# LPDDR4_SDRAM_-_2.net
KiCad netlist of a schematic drawn in Altium Designer
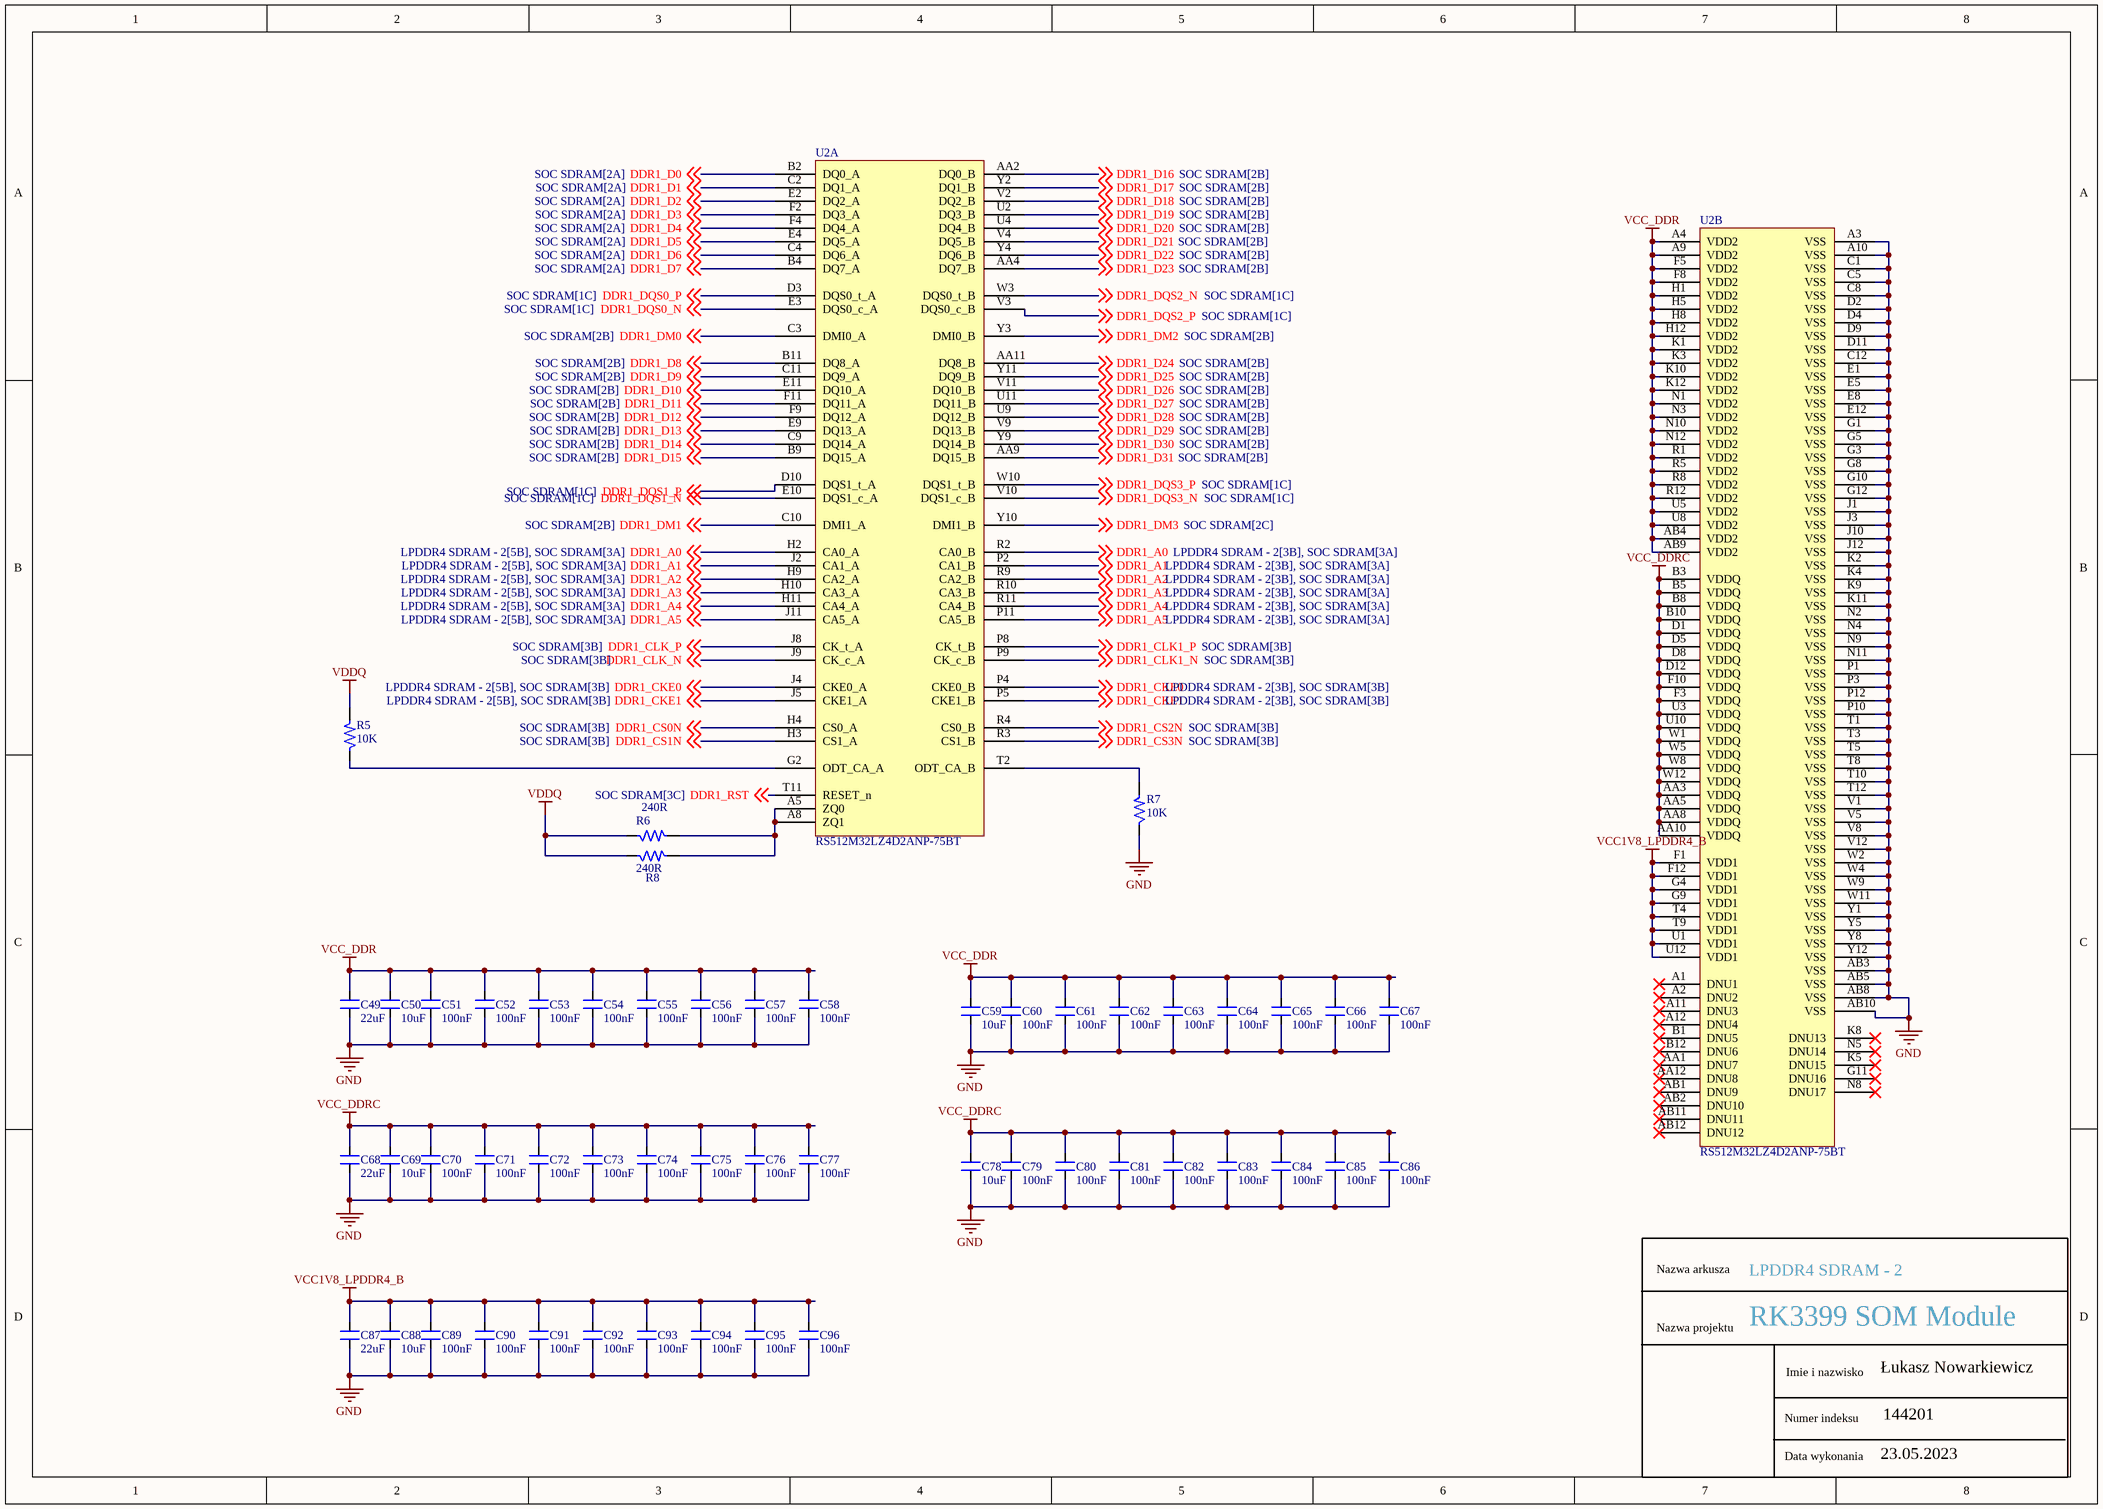
[diagram p0: LPDDR4 SDRAM - 2.SchDoc]

(export (version "E")
  (design (tool "Eeschema 10.0.6"))
  (components
    (comp (ref "C49")
      (value "22uF")
      (footprint "CAP_0603")
      (description "22µF ±20% 10V Ceramic Capacitor X5R 0603 (1608 Metric)")
      (fields
        (field (name "MANUFACTURER") "Murata Electronics")
        (field (name "MANUFACTURER PART NUMBER") "GRM188R61A226ME15D")
      )
      (libsource (lib "EsteemPCB_SOM_Course_intlib") (part "CAP_22uF-10V-20%-0603"))
    )
    (comp (ref "C50")
      (value "10uF")
      (footprint "CAP_0603")
      (description "10µF ±10% 10V Ceramic Capacitor X5R 0603 (1608 Metric)")
      (fields
        (field (name "MANUFACTURER PART NUMBER") "GRM188R61A106KE69J")
        (field (name "MANUFACTURER") "Murata Electronics")
      )
      (libsource (lib "EsteemPCB_SOM_Course_intlib") (part "CAP_10uF-10V-10%-0603"))
    )
    (comp (ref "C51")
      (value "100nF")
      (footprint "CAP_0402")
      (description "0.1µF ±10% 10V Ceramic Capacitor X7R 0402 (1005 Metric)")
      (fields
        (field (name "MANUFACTURER") "Yageo")
        (field (name "MANUFACTURER PART NUMBER") "CC0402KRX7R6BB104")
      )
      (libsource (lib "EsteemPCB_SOM_Course_intlib") (part "CAP_100nF-10V-10%-0402"))
    )
    (comp (ref "C52")
      (value "100nF")
      (footprint "CAP_0402")
      (description "0.1µF ±10% 10V Ceramic Capacitor X7R 0402 (1005 Metric)")
      (fields
        (field (name "MANUFACTURER") "Yageo")
        (field (name "MANUFACTURER PART NUMBER") "CC0402KRX7R6BB104")
      )
      (libsource (lib "EsteemPCB_SOM_Course_intlib") (part "CAP_100nF-10V-10%-0402"))
    )
    (comp (ref "C53")
      (value "100nF")
      (footprint "CAP_0402")
      (description "0.1µF ±10% 10V Ceramic Capacitor X7R 0402 (1005 Metric)")
      (fields
        (field (name "MANUFACTURER") "Yageo")
        (field (name "MANUFACTURER PART NUMBER") "CC0402KRX7R6BB104")
      )
      (libsource (lib "EsteemPCB_SOM_Course_intlib") (part "CAP_100nF-10V-10%-0402"))
    )
    (comp (ref "C54")
      (value "100nF")
      (footprint "CAP_0402")
      (description "0.1µF ±10% 10V Ceramic Capacitor X7R 0402 (1005 Metric)")
      (fields
        (field (name "MANUFACTURER") "Yageo")
        (field (name "MANUFACTURER PART NUMBER") "CC0402KRX7R6BB104")
      )
      (libsource (lib "EsteemPCB_SOM_Course_intlib") (part "CAP_100nF-10V-10%-0402"))
    )
    (comp (ref "C55")
      (value "100nF")
      (footprint "CAP_0402")
      (description "0.1µF ±10% 10V Ceramic Capacitor X7R 0402 (1005 Metric)")
      (fields
        (field (name "MANUFACTURER") "Yageo")
        (field (name "MANUFACTURER PART NUMBER") "CC0402KRX7R6BB104")
      )
      (libsource (lib "EsteemPCB_SOM_Course_intlib") (part "CAP_100nF-10V-10%-0402"))
    )
    (comp (ref "C56")
      (value "100nF")
      (footprint "CAP_0402")
      (description "0.1µF ±10% 10V Ceramic Capacitor X7R 0402 (1005 Metric)")
      (fields
        (field (name "MANUFACTURER") "Yageo")
        (field (name "MANUFACTURER PART NUMBER") "CC0402KRX7R6BB104")
      )
      (libsource (lib "EsteemPCB_SOM_Course_intlib") (part "CAP_100nF-10V-10%-0402"))
    )
    (comp (ref "C57")
      (value "100nF")
      (footprint "CAP_0402")
      (description "0.1µF ±10% 10V Ceramic Capacitor X7R 0402 (1005 Metric)")
      (fields
        (field (name "MANUFACTURER") "Yageo")
        (field (name "MANUFACTURER PART NUMBER") "CC0402KRX7R6BB104")
      )
      (libsource (lib "EsteemPCB_SOM_Course_intlib") (part "CAP_100nF-10V-10%-0402"))
    )
    (comp (ref "C58")
      (value "100nF")
      (footprint "CAP_0402")
      (description "0.1µF ±10% 10V Ceramic Capacitor X7R 0402 (1005 Metric)")
      (fields
        (field (name "MANUFACTURER") "Yageo")
        (field (name "MANUFACTURER PART NUMBER") "CC0402KRX7R6BB104")
      )
      (libsource (lib "EsteemPCB_SOM_Course_intlib") (part "CAP_100nF-10V-10%-0402"))
    )
    (comp (ref "C59")
      (value "10uF")
      (footprint "CAP_0603")
      (description "10µF ±10% 10V Ceramic Capacitor X5R 0603 (1608 Metric)")
      (fields
        (field (name "MANUFACTURER PART NUMBER") "GRM188R61A106KE69J")
        (field (name "MANUFACTURER") "Murata Electronics")
      )
      (libsource (lib "EsteemPCB_SOM_Course_intlib") (part "CAP_10uF-10V-10%-0603"))
    )
    (comp (ref "C60")
      (value "100nF")
      (footprint "CAP_0402")
      (description "0.1µF ±10% 10V Ceramic Capacitor X7R 0402 (1005 Metric)")
      (fields
        (field (name "MANUFACTURER") "Yageo")
        (field (name "MANUFACTURER PART NUMBER") "CC0402KRX7R6BB104")
      )
      (libsource (lib "EsteemPCB_SOM_Course_intlib") (part "CAP_100nF-10V-10%-0402"))
    )
    (comp (ref "C61")
      (value "100nF")
      (footprint "CAP_0402")
      (description "0.1µF ±10% 10V Ceramic Capacitor X7R 0402 (1005 Metric)")
      (fields
        (field (name "MANUFACTURER") "Yageo")
        (field (name "MANUFACTURER PART NUMBER") "CC0402KRX7R6BB104")
      )
      (libsource (lib "EsteemPCB_SOM_Course_intlib") (part "CAP_100nF-10V-10%-0402"))
    )
    (comp (ref "C62")
      (value "100nF")
      (footprint "CAP_0402")
      (description "0.1µF ±10% 10V Ceramic Capacitor X7R 0402 (1005 Metric)")
      (fields
        (field (name "MANUFACTURER") "Yageo")
        (field (name "MANUFACTURER PART NUMBER") "CC0402KRX7R6BB104")
      )
      (libsource (lib "EsteemPCB_SOM_Course_intlib") (part "CAP_100nF-10V-10%-0402"))
    )
    (comp (ref "C63")
      (value "100nF")
      (footprint "CAP_0402")
      (description "0.1µF ±10% 10V Ceramic Capacitor X7R 0402 (1005 Metric)")
      (fields
        (field (name "MANUFACTURER") "Yageo")
        (field (name "MANUFACTURER PART NUMBER") "CC0402KRX7R6BB104")
      )
      (libsource (lib "EsteemPCB_SOM_Course_intlib") (part "CAP_100nF-10V-10%-0402"))
    )
    (comp (ref "C64")
      (value "100nF")
      (footprint "CAP_0402")
      (description "0.1µF ±10% 10V Ceramic Capacitor X7R 0402 (1005 Metric)")
      (fields
        (field (name "MANUFACTURER") "Yageo")
        (field (name "MANUFACTURER PART NUMBER") "CC0402KRX7R6BB104")
      )
      (libsource (lib "EsteemPCB_SOM_Course_intlib") (part "CAP_100nF-10V-10%-0402"))
    )
    (comp (ref "C65")
      (value "100nF")
      (footprint "CAP_0402")
      (description "0.1µF ±10% 10V Ceramic Capacitor X7R 0402 (1005 Metric)")
      (fields
        (field (name "MANUFACTURER") "Yageo")
        (field (name "MANUFACTURER PART NUMBER") "CC0402KRX7R6BB104")
      )
      (libsource (lib "EsteemPCB_SOM_Course_intlib") (part "CAP_100nF-10V-10%-0402"))
    )
    (comp (ref "C66")
      (value "100nF")
      (footprint "CAP_0402")
      (description "0.1µF ±10% 10V Ceramic Capacitor X7R 0402 (1005 Metric)")
      (fields
        (field (name "MANUFACTURER") "Yageo")
        (field (name "MANUFACTURER PART NUMBER") "CC0402KRX7R6BB104")
      )
      (libsource (lib "EsteemPCB_SOM_Course_intlib") (part "CAP_100nF-10V-10%-0402"))
    )
    (comp (ref "C67")
      (value "100nF")
      (footprint "CAP_0402")
      (description "0.1µF ±10% 10V Ceramic Capacitor X7R 0402 (1005 Metric)")
      (fields
        (field (name "MANUFACTURER") "Yageo")
        (field (name "MANUFACTURER PART NUMBER") "CC0402KRX7R6BB104")
      )
      (libsource (lib "EsteemPCB_SOM_Course_intlib") (part "CAP_100nF-10V-10%-0402"))
    )
    (comp (ref "C68")
      (value "22uF")
      (footprint "CAP_0603")
      (description "22µF ±20% 10V Ceramic Capacitor X5R 0603 (1608 Metric)")
      (fields
        (field (name "MANUFACTURER") "Murata Electronics")
        (field (name "MANUFACTURER PART NUMBER") "GRM188R61A226ME15D")
      )
      (libsource (lib "EsteemPCB_SOM_Course_intlib") (part "CAP_22uF-10V-20%-0603"))
    )
    (comp (ref "C69")
      (value "10uF")
      (footprint "CAP_0603")
      (description "10µF ±10% 10V Ceramic Capacitor X5R 0603 (1608 Metric)")
      (fields
        (field (name "MANUFACTURER PART NUMBER") "GRM188R61A106KE69J")
        (field (name "MANUFACTURER") "Murata Electronics")
      )
      (libsource (lib "EsteemPCB_SOM_Course_intlib") (part "CAP_10uF-10V-10%-0603"))
    )
    (comp (ref "C70")
      (value "100nF")
      (footprint "CAP_0402")
      (description "0.1µF ±10% 10V Ceramic Capacitor X7R 0402 (1005 Metric)")
      (fields
        (field (name "MANUFACTURER") "Yageo")
        (field (name "MANUFACTURER PART NUMBER") "CC0402KRX7R6BB104")
      )
      (libsource (lib "EsteemPCB_SOM_Course_intlib") (part "CAP_100nF-10V-10%-0402"))
    )
    (comp (ref "C71")
      (value "100nF")
      (footprint "CAP_0402")
      (description "0.1µF ±10% 10V Ceramic Capacitor X7R 0402 (1005 Metric)")
      (fields
        (field (name "MANUFACTURER") "Yageo")
        (field (name "MANUFACTURER PART NUMBER") "CC0402KRX7R6BB104")
      )
      (libsource (lib "EsteemPCB_SOM_Course_intlib") (part "CAP_100nF-10V-10%-0402"))
    )
    (comp (ref "C72")
      (value "100nF")
      (footprint "CAP_0402")
      (description "0.1µF ±10% 10V Ceramic Capacitor X7R 0402 (1005 Metric)")
      (fields
        (field (name "MANUFACTURER") "Yageo")
        (field (name "MANUFACTURER PART NUMBER") "CC0402KRX7R6BB104")
      )
      (libsource (lib "EsteemPCB_SOM_Course_intlib") (part "CAP_100nF-10V-10%-0402"))
    )
    (comp (ref "C73")
      (value "100nF")
      (footprint "CAP_0402")
      (description "0.1µF ±10% 10V Ceramic Capacitor X7R 0402 (1005 Metric)")
      (fields
        (field (name "MANUFACTURER") "Yageo")
        (field (name "MANUFACTURER PART NUMBER") "CC0402KRX7R6BB104")
      )
      (libsource (lib "EsteemPCB_SOM_Course_intlib") (part "CAP_100nF-10V-10%-0402"))
    )
    (comp (ref "C74")
      (value "100nF")
      (footprint "CAP_0402")
      (description "0.1µF ±10% 10V Ceramic Capacitor X7R 0402 (1005 Metric)")
      (fields
        (field (name "MANUFACTURER") "Yageo")
        (field (name "MANUFACTURER PART NUMBER") "CC0402KRX7R6BB104")
      )
      (libsource (lib "EsteemPCB_SOM_Course_intlib") (part "CAP_100nF-10V-10%-0402"))
    )
    (comp (ref "C75")
      (value "100nF")
      (footprint "CAP_0402")
      (description "0.1µF ±10% 10V Ceramic Capacitor X7R 0402 (1005 Metric)")
      (fields
        (field (name "MANUFACTURER") "Yageo")
        (field (name "MANUFACTURER PART NUMBER") "CC0402KRX7R6BB104")
      )
      (libsource (lib "EsteemPCB_SOM_Course_intlib") (part "CAP_100nF-10V-10%-0402"))
    )
    (comp (ref "C76")
      (value "100nF")
      (footprint "CAP_0402")
      (description "0.1µF ±10% 10V Ceramic Capacitor X7R 0402 (1005 Metric)")
      (fields
        (field (name "MANUFACTURER") "Yageo")
        (field (name "MANUFACTURER PART NUMBER") "CC0402KRX7R6BB104")
      )
      (libsource (lib "EsteemPCB_SOM_Course_intlib") (part "CAP_100nF-10V-10%-0402"))
    )
    (comp (ref "C77")
      (value "100nF")
      (footprint "CAP_0402")
      (description "0.1µF ±10% 10V Ceramic Capacitor X7R 0402 (1005 Metric)")
      (fields
        (field (name "MANUFACTURER") "Yageo")
        (field (name "MANUFACTURER PART NUMBER") "CC0402KRX7R6BB104")
      )
      (libsource (lib "EsteemPCB_SOM_Course_intlib") (part "CAP_100nF-10V-10%-0402"))
    )
    (comp (ref "C78")
      (value "10uF")
      (footprint "CAP_0603")
      (description "10µF ±10% 10V Ceramic Capacitor X5R 0603 (1608 Metric)")
      (fields
        (field (name "MANUFACTURER PART NUMBER") "GRM188R61A106KE69J")
        (field (name "MANUFACTURER") "Murata Electronics")
      )
      (libsource (lib "EsteemPCB_SOM_Course_intlib") (part "CAP_10uF-10V-10%-0603"))
    )
    (comp (ref "C79")
      (value "100nF")
      (footprint "CAP_0402")
      (description "0.1µF ±10% 10V Ceramic Capacitor X7R 0402 (1005 Metric)")
      (fields
        (field (name "MANUFACTURER") "Yageo")
        (field (name "MANUFACTURER PART NUMBER") "CC0402KRX7R6BB104")
      )
      (libsource (lib "EsteemPCB_SOM_Course_intlib") (part "CAP_100nF-10V-10%-0402"))
    )
    (comp (ref "C80")
      (value "100nF")
      (footprint "CAP_0402")
      (description "0.1µF ±10% 10V Ceramic Capacitor X7R 0402 (1005 Metric)")
      (fields
        (field (name "MANUFACTURER") "Yageo")
        (field (name "MANUFACTURER PART NUMBER") "CC0402KRX7R6BB104")
      )
      (libsource (lib "EsteemPCB_SOM_Course_intlib") (part "CAP_100nF-10V-10%-0402"))
    )
    (comp (ref "C81")
      (value "100nF")
      (footprint "CAP_0402")
      (description "0.1µF ±10% 10V Ceramic Capacitor X7R 0402 (1005 Metric)")
      (fields
        (field (name "MANUFACTURER") "Yageo")
        (field (name "MANUFACTURER PART NUMBER") "CC0402KRX7R6BB104")
      )
      (libsource (lib "EsteemPCB_SOM_Course_intlib") (part "CAP_100nF-10V-10%-0402"))
    )
    (comp (ref "C82")
      (value "100nF")
      (footprint "CAP_0402")
      (description "0.1µF ±10% 10V Ceramic Capacitor X7R 0402 (1005 Metric)")
      (fields
        (field (name "MANUFACTURER") "Yageo")
        (field (name "MANUFACTURER PART NUMBER") "CC0402KRX7R6BB104")
      )
      (libsource (lib "EsteemPCB_SOM_Course_intlib") (part "CAP_100nF-10V-10%-0402"))
    )
    (comp (ref "C83")
      (value "100nF")
      (footprint "CAP_0402")
      (description "0.1µF ±10% 10V Ceramic Capacitor X7R 0402 (1005 Metric)")
      (fields
        (field (name "MANUFACTURER") "Yageo")
        (field (name "MANUFACTURER PART NUMBER") "CC0402KRX7R6BB104")
      )
      (libsource (lib "EsteemPCB_SOM_Course_intlib") (part "CAP_100nF-10V-10%-0402"))
    )
    (comp (ref "C84")
      (value "100nF")
      (footprint "CAP_0402")
      (description "0.1µF ±10% 10V Ceramic Capacitor X7R 0402 (1005 Metric)")
      (fields
        (field (name "MANUFACTURER") "Yageo")
        (field (name "MANUFACTURER PART NUMBER") "CC0402KRX7R6BB104")
      )
      (libsource (lib "EsteemPCB_SOM_Course_intlib") (part "CAP_100nF-10V-10%-0402"))
    )
    (comp (ref "C85")
      (value "100nF")
      (footprint "CAP_0402")
      (description "0.1µF ±10% 10V Ceramic Capacitor X7R 0402 (1005 Metric)")
      (fields
        (field (name "MANUFACTURER") "Yageo")
        (field (name "MANUFACTURER PART NUMBER") "CC0402KRX7R6BB104")
      )
      (libsource (lib "EsteemPCB_SOM_Course_intlib") (part "CAP_100nF-10V-10%-0402"))
    )
    (comp (ref "C86")
      (value "100nF")
      (footprint "CAP_0402")
      (description "0.1µF ±10% 10V Ceramic Capacitor X7R 0402 (1005 Metric)")
      (fields
        (field (name "MANUFACTURER") "Yageo")
        (field (name "MANUFACTURER PART NUMBER") "CC0402KRX7R6BB104")
      )
      (libsource (lib "EsteemPCB_SOM_Course_intlib") (part "CAP_100nF-10V-10%-0402"))
    )
    (comp (ref "C87")
      (value "22uF")
      (footprint "CAP_0603")
      (description "22µF ±20% 10V Ceramic Capacitor X5R 0603 (1608 Metric)")
      (fields
        (field (name "MANUFACTURER") "Murata Electronics")
        (field (name "MANUFACTURER PART NUMBER") "GRM188R61A226ME15D")
      )
      (libsource (lib "EsteemPCB_SOM_Course_intlib") (part "CAP_22uF-10V-20%-0603"))
    )
    (comp (ref "C88")
      (value "10uF")
      (footprint "CAP_0603")
      (description "10µF ±10% 10V Ceramic Capacitor X5R 0603 (1608 Metric)")
      (fields
        (field (name "MANUFACTURER PART NUMBER") "GRM188R61A106KE69J")
        (field (name "MANUFACTURER") "Murata Electronics")
      )
      (libsource (lib "EsteemPCB_SOM_Course_intlib") (part "CAP_10uF-10V-10%-0603"))
    )
    (comp (ref "C89")
      (value "100nF")
      (footprint "CAP_0402")
      (description "0.1µF ±10% 10V Ceramic Capacitor X7R 0402 (1005 Metric)")
      (fields
        (field (name "MANUFACTURER") "Yageo")
        (field (name "MANUFACTURER PART NUMBER") "CC0402KRX7R6BB104")
      )
      (libsource (lib "EsteemPCB_SOM_Course_intlib") (part "CAP_100nF-10V-10%-0402"))
    )
    (comp (ref "C90")
      (value "100nF")
      (footprint "CAP_0402")
      (description "0.1µF ±10% 10V Ceramic Capacitor X7R 0402 (1005 Metric)")
      (fields
        (field (name "MANUFACTURER") "Yageo")
        (field (name "MANUFACTURER PART NUMBER") "CC0402KRX7R6BB104")
      )
      (libsource (lib "EsteemPCB_SOM_Course_intlib") (part "CAP_100nF-10V-10%-0402"))
    )
    (comp (ref "C91")
      (value "100nF")
      (footprint "CAP_0402")
      (description "0.1µF ±10% 10V Ceramic Capacitor X7R 0402 (1005 Metric)")
      (fields
        (field (name "MANUFACTURER") "Yageo")
        (field (name "MANUFACTURER PART NUMBER") "CC0402KRX7R6BB104")
      )
      (libsource (lib "EsteemPCB_SOM_Course_intlib") (part "CAP_100nF-10V-10%-0402"))
    )
    (comp (ref "C92")
      (value "100nF")
      (footprint "CAP_0402")
      (description "0.1µF ±10% 10V Ceramic Capacitor X7R 0402 (1005 Metric)")
      (fields
        (field (name "MANUFACTURER") "Yageo")
        (field (name "MANUFACTURER PART NUMBER") "CC0402KRX7R6BB104")
      )
      (libsource (lib "EsteemPCB_SOM_Course_intlib") (part "CAP_100nF-10V-10%-0402"))
    )
    (comp (ref "C93")
      (value "100nF")
      (footprint "CAP_0402")
      (description "0.1µF ±10% 10V Ceramic Capacitor X7R 0402 (1005 Metric)")
      (fields
        (field (name "MANUFACTURER") "Yageo")
        (field (name "MANUFACTURER PART NUMBER") "CC0402KRX7R6BB104")
      )
      (libsource (lib "EsteemPCB_SOM_Course_intlib") (part "CAP_100nF-10V-10%-0402"))
    )
    (comp (ref "C94")
      (value "100nF")
      (footprint "CAP_0402")
      (description "0.1µF ±10% 10V Ceramic Capacitor X7R 0402 (1005 Metric)")
      (fields
        (field (name "MANUFACTURER") "Yageo")
        (field (name "MANUFACTURER PART NUMBER") "CC0402KRX7R6BB104")
      )
      (libsource (lib "EsteemPCB_SOM_Course_intlib") (part "CAP_100nF-10V-10%-0402"))
    )
    (comp (ref "C95")
      (value "100nF")
      (footprint "CAP_0402")
      (description "0.1µF ±10% 10V Ceramic Capacitor X7R 0402 (1005 Metric)")
      (fields
        (field (name "MANUFACTURER") "Yageo")
        (field (name "MANUFACTURER PART NUMBER") "CC0402KRX7R6BB104")
      )
      (libsource (lib "EsteemPCB_SOM_Course_intlib") (part "CAP_100nF-10V-10%-0402"))
    )
    (comp (ref "C96")
      (value "100nF")
      (footprint "CAP_0402")
      (description "0.1µF ±10% 10V Ceramic Capacitor X7R 0402 (1005 Metric)")
      (fields
        (field (name "MANUFACTURER") "Yageo")
        (field (name "MANUFACTURER PART NUMBER") "CC0402KRX7R6BB104")
      )
      (libsource (lib "EsteemPCB_SOM_Course_intlib") (part "CAP_100nF-10V-10%-0402"))
    )
    (comp (ref "R5")
      (value "10K")
      (footprint "RES_0201")
      (description "10 kOhms ±1% 0.05W, 1/20W Chip Resistor 0201 (0603 Metric) Thick Film")
      (fields
        (field (name "MANUFACTURER") "Stackpole Electronics Inc")
        (field (name "MANUFACTURER PART NUMBER") "RMCF0201FT10K0")
      )
      (libsource (lib "EsteemPCB_SOM_Course_intlib") (part "RES_10K-0.05W-1%-0201"))
    )
    (comp (ref "R6")
      (value "240R")
      (footprint "RES_0201")
      (description "240 Ohms ±1% 0.05W, 1/20W Chip Resistor 0201 (0603 Metric) Thick Film")
      (fields
        (field (name "MANUFACTURER") "Yageo")
        (field (name "MANUFACTURER PART NUMBER") "RC0201FR-07240RL")
      )
      (libsource (lib "EsteemPCB_SOM_Course_intlib") (part "RES_240R-0.05W-1%-0201"))
    )
    (comp (ref "R7")
      (value "10K")
      (footprint "RES_0201")
      (description "10 kOhms ±1% 0.05W, 1/20W Chip Resistor 0201 (0603 Metric) Thick Film")
      (fields
        (field (name "MANUFACTURER") "Stackpole Electronics Inc")
        (field (name "MANUFACTURER PART NUMBER") "RMCF0201FT10K0")
      )
      (libsource (lib "EsteemPCB_SOM_Course_intlib") (part "RES_10K-0.05W-1%-0201"))
    )
    (comp (ref "R8")
      (value "240R")
      (footprint "RES_0201")
      (description "240 Ohms ±1% 0.05W, 1/20W Chip Resistor 0201 (0603 Metric) Thick Film")
      (fields
        (field (name "MANUFACTURER") "Yageo")
        (field (name "MANUFACTURER PART NUMBER") "RC0201FR-07240RL")
      )
      (libsource (lib "EsteemPCB_SOM_Course_intlib") (part "RES_240R-0.05W-1%-0201"))
    )
    (comp (ref "U2")
      (value "RS512M32LZ4D2ANP-75BT")
      (footprint "FBGA200_SMD")
      (fields (field (name "MANUFACTURER") "RAYSON"))
      (libsource (lib "EsteemPCB_SOM_Course_intlib") (part "IC_RS512M32LZ4D2ANP-75BT"))
    )
  )
  (nets
    (net (code "1") (name "DDR1_A0") (class "Default")
      (node (ref "U2") (pin "H2") (pinfunction "CA0_A_H2") (pintype "passive"))
      (node (ref "U2") (pin "R2") (pinfunction "CA0_B_R2") (pintype "passive"))
    )
    (net (code "2") (name "DDR1_A1") (class "Default")
      (node (ref "U2") (pin "J2") (pinfunction "CA1_A_J2") (pintype "passive"))
      (node (ref "U2") (pin "P2") (pinfunction "CA1_B_P2") (pintype "passive"))
    )
    (net (code "3") (name "DDR1_A2") (class "Default")
      (node (ref "U2") (pin "H9") (pinfunction "CA2_A_H9") (pintype "passive"))
      (node (ref "U2") (pin "R9") (pinfunction "CA2_B_R9") (pintype "passive"))
    )
    (net (code "4") (name "DDR1_A3") (class "Default")
      (node (ref "U2") (pin "H10") (pinfunction "CA3_A_H10") (pintype "passive"))
      (node (ref "U2") (pin "R10") (pinfunction "CA3_B_R10") (pintype "passive"))
    )
    (net (code "5") (name "DDR1_A4") (class "Default")
      (node (ref "U2") (pin "H11") (pinfunction "CA4_A_H11") (pintype "passive"))
      (node (ref "U2") (pin "R11") (pinfunction "CA4_B_R11") (pintype "passive"))
    )
    (net (code "6") (name "DDR1_A5") (class "Default")
      (node (ref "U2") (pin "J11") (pinfunction "CA5_A_J11") (pintype "passive"))
      (node (ref "U2") (pin "P11") (pinfunction "CA5_B_P11") (pintype "passive"))
    )
    (net (code "7") (name "DDR1_CKE0") (class "Default")
      (node (ref "U2") (pin "J4") (pinfunction "CKE0_A_J4") (pintype "passive"))
      (node (ref "U2") (pin "P4") (pinfunction "CKE0_B_P4") (pintype "passive"))
    )
    (net (code "8") (name "DDR1_CKE1") (class "Default")
      (node (ref "U2") (pin "J5") (pinfunction "CKE1_A_J5") (pintype "passive"))
      (node (ref "U2") (pin "P5") (pinfunction "CKE1_B_P5") (pintype "passive"))
    )
    (net (code "9") (name "DDR1_CLK1_N") (class "Default")
      (node (ref "U2") (pin "P9") (pinfunction "CK_c_B_P9") (pintype "passive"))
    )
    (net (code "10") (name "DDR1_CLK1_P") (class "Default")
      (node (ref "U2") (pin "P8") (pinfunction "CK_t_B_P8") (pintype "passive"))
    )
    (net (code "11") (name "DDR1_CLK_N") (class "Default")
      (node (ref "U2") (pin "J9") (pinfunction "CK_c_A_J9") (pintype "passive"))
    )
    (net (code "12") (name "DDR1_CLK_P") (class "Default")
      (node (ref "U2") (pin "J8") (pinfunction "CK_t_A_J8") (pintype "passive"))
    )
    (net (code "13") (name "DDR1_CS0N") (class "Default")
      (node (ref "U2") (pin "H4") (pinfunction "CS0_A_H4") (pintype "passive"))
    )
    (net (code "14") (name "DDR1_CS1N") (class "Default")
      (node (ref "U2") (pin "H3") (pinfunction "CS1_A_H3") (pintype "passive"))
    )
    (net (code "15") (name "DDR1_CS2N") (class "Default")
      (node (ref "U2") (pin "R4") (pinfunction "CS0_B_R4") (pintype "passive"))
    )
    (net (code "16") (name "DDR1_CS3N") (class "Default")
      (node (ref "U2") (pin "R3") (pinfunction "CS1_B_R3") (pintype "passive"))
    )
    (net (code "17") (name "DDR1_D0") (class "Default")
      (node (ref "U2") (pin "B2") (pinfunction "DQ0_A_B2") (pintype "passive"))
    )
    (net (code "18") (name "DDR1_D1") (class "Default")
      (node (ref "U2") (pin "C2") (pinfunction "DQ1_A_C2") (pintype "passive"))
    )
    (net (code "19") (name "DDR1_D2") (class "Default")
      (node (ref "U2") (pin "E2") (pinfunction "DQ2_A_E2") (pintype "passive"))
    )
    (net (code "20") (name "DDR1_D3") (class "Default")
      (node (ref "U2") (pin "F2") (pinfunction "DQ3_A_F2") (pintype "passive"))
    )
    (net (code "21") (name "DDR1_D4") (class "Default")
      (node (ref "U2") (pin "F4") (pinfunction "DQ4_A_F4") (pintype "passive"))
    )
    (net (code "22") (name "DDR1_D5") (class "Default")
      (node (ref "U2") (pin "E4") (pinfunction "DQ5_A_E4") (pintype "passive"))
    )
    (net (code "23") (name "DDR1_D6") (class "Default")
      (node (ref "U2") (pin "C4") (pinfunction "DQ6_A_C4") (pintype "passive"))
    )
    (net (code "24") (name "DDR1_D7") (class "Default")
      (node (ref "U2") (pin "B4") (pinfunction "DQ7_A_B4") (pintype "passive"))
    )
    (net (code "25") (name "DDR1_D8") (class "Default")
      (node (ref "U2") (pin "B11") (pinfunction "DQ8_A_B11") (pintype "passive"))
    )
    (net (code "26") (name "DDR1_D9") (class "Default")
      (node (ref "U2") (pin "C11") (pinfunction "DQ9_A_C11") (pintype "passive"))
    )
    (net (code "27") (name "DDR1_D10") (class "Default")
      (node (ref "U2") (pin "E11") (pinfunction "DQ10_A_E11") (pintype "passive"))
    )
    (net (code "28") (name "DDR1_D11") (class "Default")
      (node (ref "U2") (pin "F11") (pinfunction "DQ11_A_F11") (pintype "passive"))
    )
    (net (code "29") (name "DDR1_D12") (class "Default")
      (node (ref "U2") (pin "F9") (pinfunction "DQ12_A_F9") (pintype "passive"))
    )
    (net (code "30") (name "DDR1_D13") (class "Default")
      (node (ref "U2") (pin "E9") (pinfunction "DQ13_A_E9") (pintype "passive"))
    )
    (net (code "31") (name "DDR1_D14") (class "Default")
      (node (ref "U2") (pin "C9") (pinfunction "DQ14_A_C9") (pintype "passive"))
    )
    (net (code "32") (name "DDR1_D15") (class "Default")
      (node (ref "U2") (pin "B9") (pinfunction "DQ15_A_B9") (pintype "passive"))
    )
    (net (code "33") (name "DDR1_D16") (class "Default")
      (node (ref "U2") (pin "AA2") (pinfunction "DQ0_B_AA2") (pintype "passive"))
    )
    (net (code "34") (name "DDR1_D17") (class "Default")
      (node (ref "U2") (pin "Y2") (pinfunction "DQ1_B_Y2") (pintype "passive"))
    )
    (net (code "35") (name "DDR1_D18") (class "Default")
      (node (ref "U2") (pin "V2") (pinfunction "DQ2_B_V2") (pintype "passive"))
    )
    (net (code "36") (name "DDR1_D19") (class "Default")
      (node (ref "U2") (pin "U2") (pinfunction "DQ3_B_U2") (pintype "passive"))
    )
    (net (code "37") (name "DDR1_D20") (class "Default")
      (node (ref "U2") (pin "U4") (pinfunction "DQ4_B_U4") (pintype "passive"))
    )
    (net (code "38") (name "DDR1_D21") (class "Default")
      (node (ref "U2") (pin "V4") (pinfunction "DQ5_B_V4") (pintype "passive"))
    )
    (net (code "39") (name "DDR1_D22") (class "Default")
      (node (ref "U2") (pin "Y4") (pinfunction "DQ6_B_Y4") (pintype "passive"))
    )
    (net (code "40") (name "DDR1_D23") (class "Default")
      (node (ref "U2") (pin "AA4") (pinfunction "DQ7_B_AA4") (pintype "passive"))
    )
    (net (code "41") (name "DDR1_D24") (class "Default")
      (node (ref "U2") (pin "AA11") (pinfunction "DQ8_B_AA11") (pintype "passive"))
    )
    (net (code "42") (name "DDR1_D25") (class "Default")
      (node (ref "U2") (pin "Y11") (pinfunction "DQ9_B_Y11") (pintype "passive"))
    )
    (net (code "43") (name "DDR1_D26") (class "Default")
      (node (ref "U2") (pin "V11") (pinfunction "DQ10_B_V11") (pintype "passive"))
    )
    (net (code "44") (name "DDR1_D27") (class "Default")
      (node (ref "U2") (pin "U11") (pinfunction "DQ11_B_U11") (pintype "passive"))
    )
    (net (code "45") (name "DDR1_D28") (class "Default")
      (node (ref "U2") (pin "U9") (pinfunction "DQ12_B_U9") (pintype "passive"))
    )
    (net (code "46") (name "DDR1_D29") (class "Default")
      (node (ref "U2") (pin "V9") (pinfunction "DQ13_B_V9") (pintype "passive"))
    )
    (net (code "47") (name "DDR1_D30") (class "Default")
      (node (ref "U2") (pin "Y9") (pinfunction "DQ14_B_Y9") (pintype "passive"))
    )
    (net (code "48") (name "DDR1_D31") (class "Default")
      (node (ref "U2") (pin "AA9") (pinfunction "DQ15_B_AA9") (pintype "passive"))
    )
    (net (code "49") (name "DDR1_DM0") (class "Default")
      (node (ref "U2") (pin "C3") (pinfunction "DMI0_A_C3") (pintype "passive"))
    )
    (net (code "50") (name "DDR1_DM1") (class "Default")
      (node (ref "U2") (pin "C10") (pinfunction "DMI1_A_C10") (pintype "passive"))
    )
    (net (code "51") (name "DDR1_DM2") (class "Default")
      (node (ref "U2") (pin "Y3") (pinfunction "DMI0_B_Y3") (pintype "passive"))
    )
    (net (code "52") (name "DDR1_DM3") (class "Default")
      (node (ref "U2") (pin "Y10") (pinfunction "DMI1_B_Y10") (pintype "passive"))
    )
    (net (code "53") (name "DDR1_DQS0_N") (class "Default")
      (node (ref "U2") (pin "E3") (pinfunction "DQS0_c_A_E3") (pintype "passive"))
    )
    (net (code "54") (name "DDR1_DQS0_P") (class "Default")
      (node (ref "U2") (pin "D3") (pinfunction "DQS0_t_A_D3") (pintype "passive"))
    )
    (net (code "55") (name "DDR1_DQS1_N") (class "Default")
      (node (ref "U2") (pin "E10") (pinfunction "DQS1_c_A_E10") (pintype "passive"))
    )
    (net (code "56") (name "DDR1_DQS1_P") (class "Default")
      (node (ref "U2") (pin "D10") (pinfunction "DQS1_t_A_D10") (pintype "passive"))
    )
    (net (code "57") (name "DDR1_DQS2_N") (class "Default")
      (node (ref "U2") (pin "W3") (pinfunction "DQS0_t_B_W3") (pintype "passive"))
    )
    (net (code "58") (name "DDR1_DQS2_P") (class "Default")
      (node (ref "U2") (pin "V3") (pinfunction "DQS0_c_B_V3") (pintype "passive"))
    )
    (net (code "59") (name "DDR1_DQS3_N") (class "Default")
      (node (ref "U2") (pin "V10") (pinfunction "DQS1_c_B_V10") (pintype "passive"))
    )
    (net (code "60") (name "DDR1_DQS3_P") (class "Default")
      (node (ref "U2") (pin "W10") (pinfunction "DQS1_t_B_W10") (pintype "passive"))
    )
    (net (code "61") (name "DDR1_RST") (class "Default")
      (node (ref "U2") (pin "T11") (pinfunction "RESET_n_T11") (pintype "passive"))
    )
    (net (code "62") (name "GND") (class "Default")
      (node (ref "C49") (pin "1") (pinfunction "1_1") (pintype "passive"))
      (node (ref "C50") (pin "1") (pinfunction "1_1") (pintype "passive"))
      (node (ref "C51") (pin "1") (pinfunction "1_1") (pintype "passive"))
      (node (ref "C52") (pin "1") (pinfunction "1_1") (pintype "passive"))
      (node (ref "C53") (pin "1") (pinfunction "1_1") (pintype "passive"))
      (node (ref "C54") (pin "1") (pinfunction "1_1") (pintype "passive"))
      (node (ref "C55") (pin "1") (pinfunction "1_1") (pintype "passive"))
      (node (ref "C56") (pin "1") (pinfunction "1_1") (pintype "passive"))
      (node (ref "C57") (pin "1") (pinfunction "1_1") (pintype "passive"))
      (node (ref "C58") (pin "1") (pinfunction "1_1") (pintype "passive"))
      (node (ref "C59") (pin "1") (pinfunction "1_1") (pintype "passive"))
      (node (ref "C60") (pin "1") (pinfunction "1_1") (pintype "passive"))
      (node (ref "C61") (pin "1") (pinfunction "1_1") (pintype "passive"))
      (node (ref "C62") (pin "1") (pinfunction "1_1") (pintype "passive"))
      (node (ref "C63") (pin "1") (pinfunction "1_1") (pintype "passive"))
      (node (ref "C64") (pin "1") (pinfunction "1_1") (pintype "passive"))
      (node (ref "C65") (pin "1") (pinfunction "1_1") (pintype "passive"))
      (node (ref "C66") (pin "1") (pinfunction "1_1") (pintype "passive"))
      (node (ref "C67") (pin "1") (pinfunction "1_1") (pintype "passive"))
      (node (ref "C68") (pin "1") (pinfunction "1_1") (pintype "passive"))
      (node (ref "C69") (pin "1") (pinfunction "1_1") (pintype "passive"))
      (node (ref "C70") (pin "1") (pinfunction "1_1") (pintype "passive"))
      (node (ref "C71") (pin "1") (pinfunction "1_1") (pintype "passive"))
      (node (ref "C72") (pin "1") (pinfunction "1_1") (pintype "passive"))
      (node (ref "C73") (pin "1") (pinfunction "1_1") (pintype "passive"))
      (node (ref "C74") (pin "1") (pinfunction "1_1") (pintype "passive"))
      (node (ref "C75") (pin "1") (pinfunction "1_1") (pintype "passive"))
      (node (ref "C76") (pin "1") (pinfunction "1_1") (pintype "passive"))
      (node (ref "C77") (pin "1") (pinfunction "1_1") (pintype "passive"))
      (node (ref "C78") (pin "1") (pinfunction "1_1") (pintype "passive"))
      (node (ref "C79") (pin "1") (pinfunction "1_1") (pintype "passive"))
      (node (ref "C80") (pin "1") (pinfunction "1_1") (pintype "passive"))
      (node (ref "C81") (pin "1") (pinfunction "1_1") (pintype "passive"))
      (node (ref "C82") (pin "1") (pinfunction "1_1") (pintype "passive"))
      (node (ref "C83") (pin "1") (pinfunction "1_1") (pintype "passive"))
      (node (ref "C84") (pin "1") (pinfunction "1_1") (pintype "passive"))
      (node (ref "C85") (pin "1") (pinfunction "1_1") (pintype "passive"))
      (node (ref "C86") (pin "1") (pinfunction "1_1") (pintype "passive"))
      (node (ref "C87") (pin "1") (pinfunction "1_1") (pintype "passive"))
      (node (ref "C88") (pin "1") (pinfunction "1_1") (pintype "passive"))
      (node (ref "C89") (pin "1") (pinfunction "1_1") (pintype "passive"))
      (node (ref "C90") (pin "1") (pinfunction "1_1") (pintype "passive"))
      (node (ref "C91") (pin "1") (pinfunction "1_1") (pintype "passive"))
      (node (ref "C92") (pin "1") (pinfunction "1_1") (pintype "passive"))
      (node (ref "C93") (pin "1") (pinfunction "1_1") (pintype "passive"))
      (node (ref "C94") (pin "1") (pinfunction "1_1") (pintype "passive"))
      (node (ref "C95") (pin "1") (pinfunction "1_1") (pintype "passive"))
      (node (ref "C96") (pin "1") (pinfunction "1_1") (pintype "passive"))
      (node (ref "R7") (pin "1") (pinfunction "1_1") (pintype "passive"))
      (node (ref "U2") (pin "A10") (pinfunction "VSS_A10") (pintype "passive"))
      (node (ref "U2") (pin "A3") (pinfunction "VSS_A3") (pintype "passive"))
      (node (ref "U2") (pin "AB10") (pinfunction "VSS_AB10") (pintype "passive"))
      (node (ref "U2") (pin "AB3") (pinfunction "VSS_AB3") (pintype "passive"))
      (node (ref "U2") (pin "AB5") (pinfunction "VSS_AB5") (pintype "passive"))
      (node (ref "U2") (pin "AB8") (pinfunction "VSS_AB8") (pintype "passive"))
      (node (ref "U2") (pin "C1") (pinfunction "VSS_C1") (pintype "passive"))
      (node (ref "U2") (pin "C12") (pinfunction "VSS_C12") (pintype "passive"))
      (node (ref "U2") (pin "C5") (pinfunction "VSS_C5") (pintype "passive"))
      (node (ref "U2") (pin "C8") (pinfunction "VSS_C8") (pintype "passive"))
      (node (ref "U2") (pin "D11") (pinfunction "VSS_D11") (pintype "passive"))
      (node (ref "U2") (pin "D2") (pinfunction "VSS_D2") (pintype "passive"))
      (node (ref "U2") (pin "D4") (pinfunction "VSS_D4") (pintype "passive"))
      (node (ref "U2") (pin "D9") (pinfunction "VSS_D9") (pintype "passive"))
      (node (ref "U2") (pin "E1") (pinfunction "VSS_E1") (pintype "passive"))
      (node (ref "U2") (pin "E12") (pinfunction "VSS_E12") (pintype "passive"))
      (node (ref "U2") (pin "E5") (pinfunction "VSS_E5") (pintype "passive"))
      (node (ref "U2") (pin "E8") (pinfunction "VSS_E8") (pintype "passive"))
      (node (ref "U2") (pin "G1") (pinfunction "VSS_G1") (pintype "passive"))
      (node (ref "U2") (pin "G10") (pinfunction "VSS_G10") (pintype "passive"))
      (node (ref "U2") (pin "G12") (pinfunction "VSS_G12") (pintype "passive"))
      (node (ref "U2") (pin "G3") (pinfunction "VSS_G3") (pintype "passive"))
      (node (ref "U2") (pin "G5") (pinfunction "VSS_G5") (pintype "passive"))
      (node (ref "U2") (pin "G8") (pinfunction "VSS_G8") (pintype "passive"))
      (node (ref "U2") (pin "J1") (pinfunction "VSS_J1") (pintype "passive"))
      (node (ref "U2") (pin "J10") (pinfunction "VSS_J10") (pintype "passive"))
      (node (ref "U2") (pin "J12") (pinfunction "VSS_J12") (pintype "passive"))
      (node (ref "U2") (pin "J3") (pinfunction "VSS_J3") (pintype "passive"))
      (node (ref "U2") (pin "K11") (pinfunction "VSS_K11") (pintype "passive"))
      (node (ref "U2") (pin "K2") (pinfunction "VSS_K2") (pintype "passive"))
      (node (ref "U2") (pin "K4") (pinfunction "VSS_K4") (pintype "passive"))
      (node (ref "U2") (pin "K9") (pinfunction "VSS_K9") (pintype "passive"))
      (node (ref "U2") (pin "N11") (pinfunction "VSS_N11") (pintype "passive"))
      (node (ref "U2") (pin "N2") (pinfunction "VSS_N2") (pintype "passive"))
      (node (ref "U2") (pin "N4") (pinfunction "VSS_N4") (pintype "passive"))
      (node (ref "U2") (pin "N9") (pinfunction "VSS_N9") (pintype "passive"))
      (node (ref "U2") (pin "P1") (pinfunction "VSS_P1") (pintype "passive"))
      (node (ref "U2") (pin "P10") (pinfunction "VSS_P10") (pintype "passive"))
      (node (ref "U2") (pin "P12") (pinfunction "VSS_P12") (pintype "passive"))
      (node (ref "U2") (pin "P3") (pinfunction "VSS_P3") (pintype "passive"))
      (node (ref "U2") (pin "T1") (pinfunction "VSS_T1") (pintype "passive"))
      (node (ref "U2") (pin "T10") (pinfunction "VSS_T10") (pintype "passive"))
      (node (ref "U2") (pin "T12") (pinfunction "VSS_T12") (pintype "passive"))
      (node (ref "U2") (pin "T3") (pinfunction "VSS_T3") (pintype "passive"))
      (node (ref "U2") (pin "T5") (pinfunction "VSS_T5") (pintype "passive"))
      (node (ref "U2") (pin "T8") (pinfunction "VSS_T8") (pintype "passive"))
      (node (ref "U2") (pin "V1") (pinfunction "VSS_V1") (pintype "passive"))
      (node (ref "U2") (pin "V12") (pinfunction "VSS_V12") (pintype "passive"))
      (node (ref "U2") (pin "V5") (pinfunction "VSS_V5") (pintype "passive"))
      (node (ref "U2") (pin "V8") (pinfunction "VSS_V8") (pintype "passive"))
      (node (ref "U2") (pin "W11") (pinfunction "VSS_W11") (pintype "passive"))
      (node (ref "U2") (pin "W2") (pinfunction "VSS_W2") (pintype "passive"))
      (node (ref "U2") (pin "W4") (pinfunction "VSS_W4") (pintype "passive"))
      (node (ref "U2") (pin "W9") (pinfunction "VSS_W9") (pintype "passive"))
      (node (ref "U2") (pin "Y1") (pinfunction "VSS_Y1") (pintype "passive"))
      (node (ref "U2") (pin "Y12") (pinfunction "VSS_Y12") (pintype "passive"))
      (node (ref "U2") (pin "Y5") (pinfunction "VSS_Y5") (pintype "passive"))
      (node (ref "U2") (pin "Y8") (pinfunction "VSS_Y8") (pintype "passive"))
    )
    (net (code "63") (name "Net-(U2A-ODT_CA_A)") (class "Default")
      (node (ref "R5") (pin "1") (pinfunction "1_1") (pintype "passive"))
      (node (ref "U2") (pin "G2") (pinfunction "ODT_CA_A_G2") (pintype "passive"))
    )
    (net (code "64") (name "Net-(U2A-ODT_CA_B)") (class "Default")
      (node (ref "R7") (pin "2") (pinfunction "2_2") (pintype "passive"))
      (node (ref "U2") (pin "T2") (pinfunction "ODT_CA_B_T2") (pintype "passive"))
    )
    (net (code "65") (name "Net-(U2A-ZQ0)") (class "Default")
      (node (ref "R6") (pin "2") (pinfunction "2_2") (pintype "passive"))
      (node (ref "R8") (pin "2") (pinfunction "2_2") (pintype "passive"))
      (node (ref "U2") (pin "A5") (pinfunction "ZQ0_A5") (pintype "passive"))
      (node (ref "U2") (pin "A8") (pinfunction "ZQ1_A8") (pintype "passive"))
    )
    (net (code "66") (name "VCC1V8_LPDDR4_B") (class "Default")
      (node (ref "C87") (pin "2") (pinfunction "2_2") (pintype "passive"))
      (node (ref "C88") (pin "2") (pinfunction "2_2") (pintype "passive"))
      (node (ref "C89") (pin "2") (pinfunction "2_2") (pintype "passive"))
      (node (ref "C90") (pin "2") (pinfunction "2_2") (pintype "passive"))
      (node (ref "C91") (pin "2") (pinfunction "2_2") (pintype "passive"))
      (node (ref "C92") (pin "2") (pinfunction "2_2") (pintype "passive"))
      (node (ref "C93") (pin "2") (pinfunction "2_2") (pintype "passive"))
      (node (ref "C94") (pin "2") (pinfunction "2_2") (pintype "passive"))
      (node (ref "C95") (pin "2") (pinfunction "2_2") (pintype "passive"))
      (node (ref "C96") (pin "2") (pinfunction "2_2") (pintype "passive"))
      (node (ref "U2") (pin "F1") (pinfunction "VDD1_F1") (pintype "passive"))
      (node (ref "U2") (pin "F12") (pinfunction "VDD1_F12") (pintype "passive"))
      (node (ref "U2") (pin "G4") (pinfunction "VDD1_G4") (pintype "passive"))
      (node (ref "U2") (pin "G9") (pinfunction "VDD1_G9") (pintype "passive"))
      (node (ref "U2") (pin "T4") (pinfunction "VDD1_T4") (pintype "passive"))
      (node (ref "U2") (pin "T9") (pinfunction "VDD1_T9") (pintype "passive"))
      (node (ref "U2") (pin "U1") (pinfunction "VDD1_U1") (pintype "passive"))
      (node (ref "U2") (pin "U12") (pinfunction "VDD1_U12") (pintype "passive"))
    )
    (net (code "67") (name "VCC_DDR") (class "Default")
      (node (ref "C49") (pin "2") (pinfunction "2_2") (pintype "passive"))
      (node (ref "C50") (pin "2") (pinfunction "2_2") (pintype "passive"))
      (node (ref "C51") (pin "2") (pinfunction "2_2") (pintype "passive"))
      (node (ref "C52") (pin "2") (pinfunction "2_2") (pintype "passive"))
      (node (ref "C53") (pin "2") (pinfunction "2_2") (pintype "passive"))
      (node (ref "C54") (pin "2") (pinfunction "2_2") (pintype "passive"))
      (node (ref "C55") (pin "2") (pinfunction "2_2") (pintype "passive"))
      (node (ref "C56") (pin "2") (pinfunction "2_2") (pintype "passive"))
      (node (ref "C57") (pin "2") (pinfunction "2_2") (pintype "passive"))
      (node (ref "C58") (pin "2") (pinfunction "2_2") (pintype "passive"))
      (node (ref "C59") (pin "2") (pinfunction "2_2") (pintype "passive"))
      (node (ref "C60") (pin "2") (pinfunction "2_2") (pintype "passive"))
      (node (ref "C61") (pin "2") (pinfunction "2_2") (pintype "passive"))
      (node (ref "C62") (pin "2") (pinfunction "2_2") (pintype "passive"))
      (node (ref "C63") (pin "2") (pinfunction "2_2") (pintype "passive"))
      (node (ref "C64") (pin "2") (pinfunction "2_2") (pintype "passive"))
      (node (ref "C65") (pin "2") (pinfunction "2_2") (pintype "passive"))
      (node (ref "C66") (pin "2") (pinfunction "2_2") (pintype "passive"))
      (node (ref "C67") (pin "2") (pinfunction "2_2") (pintype "passive"))
      (node (ref "U2") (pin "A4") (pinfunction "VDD2_A4") (pintype "passive"))
      (node (ref "U2") (pin "A9") (pinfunction "VDD2_A9") (pintype "passive"))
      (node (ref "U2") (pin "AB4") (pinfunction "VDD2_AB4") (pintype "passive"))
      (node (ref "U2") (pin "AB9") (pinfunction "VDD2_AB9") (pintype "passive"))
      (node (ref "U2") (pin "F5") (pinfunction "VDD2_F5") (pintype "passive"))
      (node (ref "U2") (pin "F8") (pinfunction "VDD2_F8") (pintype "passive"))
      (node (ref "U2") (pin "H1") (pinfunction "VDD2_H1") (pintype "passive"))
      (node (ref "U2") (pin "H12") (pinfunction "VDD2_H12") (pintype "passive"))
      (node (ref "U2") (pin "H5") (pinfunction "VDD2_H5") (pintype "passive"))
      (node (ref "U2") (pin "H8") (pinfunction "VDD2_H8") (pintype "passive"))
      (node (ref "U2") (pin "K1") (pinfunction "VDD2_K1") (pintype "passive"))
      (node (ref "U2") (pin "K10") (pinfunction "VDD2_K10") (pintype "passive"))
      (node (ref "U2") (pin "K12") (pinfunction "VDD2_K12") (pintype "passive"))
      (node (ref "U2") (pin "K3") (pinfunction "VDD2_K3") (pintype "passive"))
      (node (ref "U2") (pin "N1") (pinfunction "VDD2_N1") (pintype "passive"))
      (node (ref "U2") (pin "N10") (pinfunction "VDD2_N10") (pintype "passive"))
      (node (ref "U2") (pin "N12") (pinfunction "VDD2_N12") (pintype "passive"))
      (node (ref "U2") (pin "N3") (pinfunction "VDD2_N3") (pintype "passive"))
      (node (ref "U2") (pin "R1") (pinfunction "VDD2_R1") (pintype "passive"))
      (node (ref "U2") (pin "R12") (pinfunction "VDD2_R12") (pintype "passive"))
      (node (ref "U2") (pin "R5") (pinfunction "VDD2_R5") (pintype "passive"))
      (node (ref "U2") (pin "R8") (pinfunction "VDD2_R8") (pintype "passive"))
      (node (ref "U2") (pin "U5") (pinfunction "VDD2_U5") (pintype "passive"))
      (node (ref "U2") (pin "U8") (pinfunction "VDD2_U8") (pintype "passive"))
    )
    (net (code "68") (name "VCC_DDRC") (class "Default")
      (node (ref "C68") (pin "2") (pinfunction "2_2") (pintype "passive"))
      (node (ref "C69") (pin "2") (pinfunction "2_2") (pintype "passive"))
      (node (ref "C70") (pin "2") (pinfunction "2_2") (pintype "passive"))
      (node (ref "C71") (pin "2") (pinfunction "2_2") (pintype "passive"))
      (node (ref "C72") (pin "2") (pinfunction "2_2") (pintype "passive"))
      (node (ref "C73") (pin "2") (pinfunction "2_2") (pintype "passive"))
      (node (ref "C74") (pin "2") (pinfunction "2_2") (pintype "passive"))
      (node (ref "C75") (pin "2") (pinfunction "2_2") (pintype "passive"))
      (node (ref "C76") (pin "2") (pinfunction "2_2") (pintype "passive"))
      (node (ref "C77") (pin "2") (pinfunction "2_2") (pintype "passive"))
      (node (ref "C78") (pin "2") (pinfunction "2_2") (pintype "passive"))
      (node (ref "C79") (pin "2") (pinfunction "2_2") (pintype "passive"))
      (node (ref "C80") (pin "2") (pinfunction "2_2") (pintype "passive"))
      (node (ref "C81") (pin "2") (pinfunction "2_2") (pintype "passive"))
      (node (ref "C82") (pin "2") (pinfunction "2_2") (pintype "passive"))
      (node (ref "C83") (pin "2") (pinfunction "2_2") (pintype "passive"))
      (node (ref "C84") (pin "2") (pinfunction "2_2") (pintype "passive"))
      (node (ref "C85") (pin "2") (pinfunction "2_2") (pintype "passive"))
      (node (ref "C86") (pin "2") (pinfunction "2_2") (pintype "passive"))
      (node (ref "U2") (pin "AA10") (pinfunction "VDDQ_AA10") (pintype "passive"))
      (node (ref "U2") (pin "AA3") (pinfunction "VDDQ_AA3") (pintype "passive"))
      (node (ref "U2") (pin "AA5") (pinfunction "VDDQ_AA5") (pintype "passive"))
      (node (ref "U2") (pin "AA8") (pinfunction "VDDQ_AA8") (pintype "passive"))
      (node (ref "U2") (pin "B10") (pinfunction "VDDQ_B10") (pintype "passive"))
      (node (ref "U2") (pin "B3") (pinfunction "VDDQ_B3") (pintype "passive"))
      (node (ref "U2") (pin "B5") (pinfunction "VDDQ_B5") (pintype "passive"))
      (node (ref "U2") (pin "B8") (pinfunction "VDDQ_B8") (pintype "passive"))
      (node (ref "U2") (pin "D1") (pinfunction "VDDQ_D1") (pintype "passive"))
      (node (ref "U2") (pin "D12") (pinfunction "VDDQ_D12") (pintype "passive"))
      (node (ref "U2") (pin "D5") (pinfunction "VDDQ_D5") (pintype "passive"))
      (node (ref "U2") (pin "D8") (pinfunction "VDDQ_D8") (pintype "passive"))
      (node (ref "U2") (pin "F10") (pinfunction "VDDQ_F10") (pintype "passive"))
      (node (ref "U2") (pin "F3") (pinfunction "VDDQ_F3") (pintype "passive"))
      (node (ref "U2") (pin "U10") (pinfunction "VDDQ_U10") (pintype "passive"))
      (node (ref "U2") (pin "U3") (pinfunction "VDDQ_U3") (pintype "passive"))
      (node (ref "U2") (pin "W1") (pinfunction "VDDQ_W1") (pintype "passive"))
      (node (ref "U2") (pin "W12") (pinfunction "VDDQ_W12") (pintype "passive"))
      (node (ref "U2") (pin "W5") (pinfunction "VDDQ_W5") (pintype "passive"))
      (node (ref "U2") (pin "W8") (pinfunction "VDDQ_W8") (pintype "passive"))
    )
    (net (code "69") (name "VDDQ") (class "Default")
      (node (ref "R5") (pin "2") (pinfunction "2_2") (pintype "passive"))
      (node (ref "R6") (pin "1") (pinfunction "1_1") (pintype "passive"))
      (node (ref "R8") (pin "1") (pinfunction "1_1") (pintype "passive"))
    )
    (net (code "70") (name "unconnected-(U2B-DNU1-PadA1)") (class "Default")
      (node (ref "U2") (pin "A1") (pinfunction "DNU1_A1") (pintype "passive+no_connect"))
    )
    (net (code "71") (name "unconnected-(U2B-DNU2-PadA2)") (class "Default")
      (node (ref "U2") (pin "A2") (pinfunction "DNU2_A2") (pintype "passive+no_connect"))
    )
    (net (code "72") (name "unconnected-(U2B-DNU3-PadA11)") (class "Default")
      (node (ref "U2") (pin "A11") (pinfunction "DNU3_A11") (pintype "passive+no_connect"))
    )
    (net (code "73") (name "unconnected-(U2B-DNU4-PadA12)") (class "Default")
      (node (ref "U2") (pin "A12") (pinfunction "DNU4_A12") (pintype "passive+no_connect"))
    )
    (net (code "74") (name "unconnected-(U2B-DNU5-PadB1)") (class "Default")
      (node (ref "U2") (pin "B1") (pinfunction "DNU5_B1") (pintype "passive+no_connect"))
    )
    (net (code "75") (name "unconnected-(U2B-DNU6-PadB12)") (class "Default")
      (node (ref "U2") (pin "B12") (pinfunction "DNU6_B12") (pintype "passive+no_connect"))
    )
    (net (code "76") (name "unconnected-(U2B-DNU7-PadAA1)") (class "Default")
      (node (ref "U2") (pin "AA1") (pinfunction "DNU7_AA1") (pintype "passive+no_connect"))
    )
    (net (code "77") (name "unconnected-(U2B-DNU8-PadAA12)") (class "Default")
      (node (ref "U2") (pin "AA12") (pinfunction "DNU8_AA12") (pintype "passive+no_connect"))
    )
    (net (code "78") (name "unconnected-(U2B-DNU9-PadAB1)") (class "Default")
      (node (ref "U2") (pin "AB1") (pinfunction "DNU9_AB1") (pintype "passive+no_connect"))
    )
    (net (code "79") (name "unconnected-(U2B-DNU10-PadAB2)") (class "Default")
      (node (ref "U2") (pin "AB2") (pinfunction "DNU10_AB2") (pintype "passive+no_connect"))
    )
    (net (code "80") (name "unconnected-(U2B-DNU11-PadAB11)") (class "Default")
      (node (ref "U2") (pin "AB11") (pinfunction "DNU11_AB11") (pintype "passive+no_connect"))
    )
    (net (code "81") (name "unconnected-(U2B-DNU12-PadAB12)") (class "Default")
      (node (ref "U2") (pin "AB12") (pinfunction "DNU12_AB12") (pintype "passive+no_connect"))
    )
    (net (code "82") (name "unconnected-(U2B-DNU13-PadK8)") (class "Default")
      (node (ref "U2") (pin "K8") (pinfunction "DNU13_K8") (pintype "passive+no_connect"))
    )
    (net (code "83") (name "unconnected-(U2B-DNU14-PadN5)") (class "Default")
      (node (ref "U2") (pin "N5") (pinfunction "DNU14_N5") (pintype "passive+no_connect"))
    )
    (net (code "84") (name "unconnected-(U2B-DNU15-PadK5)") (class "Default")
      (node (ref "U2") (pin "K5") (pinfunction "DNU15_K5") (pintype "passive+no_connect"))
    )
    (net (code "85") (name "unconnected-(U2B-DNU16-PadG11)") (class "Default")
      (node (ref "U2") (pin "G11") (pinfunction "DNU16_G11") (pintype "passive+no_connect"))
    )
    (net (code "86") (name "unconnected-(U2B-DNU17-PadN8)") (class "Default")
      (node (ref "U2") (pin "N8") (pinfunction "DNU17_N8") (pintype "passive+no_connect"))
    )
  )
)
